# Mechanical.net
KiCad netlist of a schematic drawn in Altium Designer
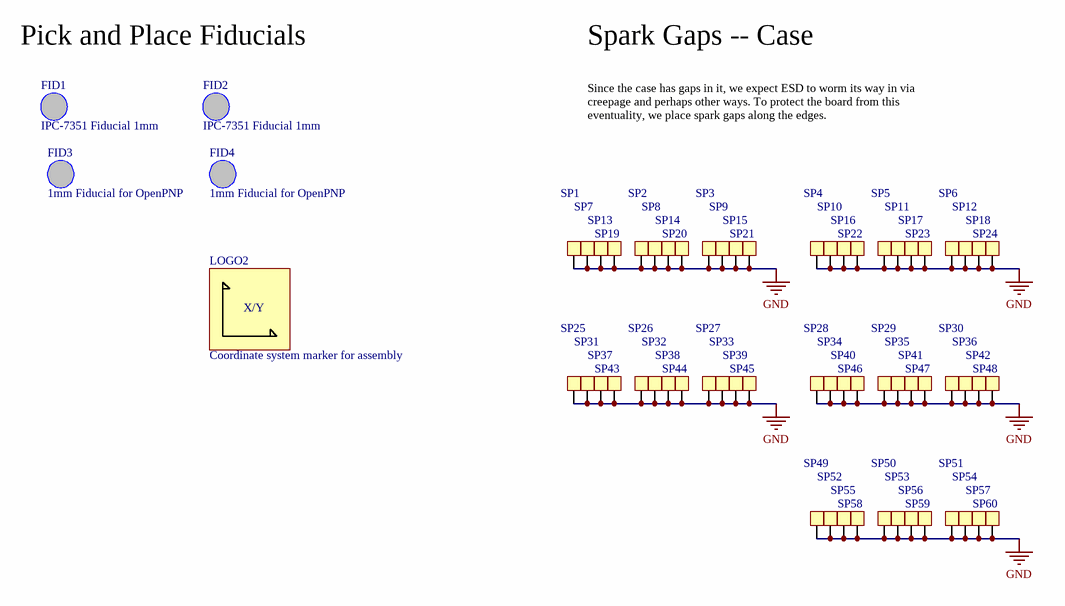
[diagram p0: Mechanical.SchDoc]

(export (version "E")
  (design (tool "Eeschema 10.0.6"))
  (components
    (comp (ref "FID1")
      (value "IPC-7351 Fiducial 1mm")
      (footprint "FIDUCIAL_1.5")
      (libsource (lib "Mechanical") (part "FIDUCIAL_1.5"))
    )
    (comp (ref "FID2")
      (value "IPC-7351 Fiducial 1mm")
      (footprint "FIDUCIAL_1.5")
      (libsource (lib "Mechanical") (part "FIDUCIAL_1.5"))
    )
    (comp (ref "FID3")
      (value "1mm Fiducial for OpenPNP")
      (footprint "FIDUCIAL-NEW")
      (libsource (lib "Mechanical") (part "FIDUCIAL_NEW"))
    )
    (comp (ref "FID4")
      (value "1mm Fiducial for OpenPNP")
      (footprint "FIDUCIAL-NEW")
      (libsource (lib "Mechanical") (part "FIDUCIAL_NEW"))
    )
    (comp (ref "LOGO2")
      (value "Coordinate system marker for assembly")
      (footprint "Coordinate System")
      (libsource (lib "Graphics") (part "CoordinateSystem"))
    )
    (comp (ref "SP1")
      (value "Spark Gap")
      (footprint "SparkGap")
      (description "Open square pad for spark gapping")
      (libsource (lib "PCBFeatures") (part "Spark Gap"))
    )
    (comp (ref "SP2")
      (value "Spark Gap")
      (footprint "SparkGap")
      (description "Open square pad for spark gapping")
      (libsource (lib "PCBFeatures") (part "Spark Gap"))
    )
    (comp (ref "SP3")
      (value "Spark Gap")
      (footprint "SparkGap")
      (description "Open square pad for spark gapping")
      (libsource (lib "PCBFeatures") (part "Spark Gap"))
    )
    (comp (ref "SP4")
      (value "Spark Gap")
      (footprint "SparkGap")
      (description "Open square pad for spark gapping")
      (libsource (lib "PCBFeatures") (part "Spark Gap"))
    )
    (comp (ref "SP5")
      (value "Spark Gap")
      (footprint "SparkGap")
      (description "Open square pad for spark gapping")
      (libsource (lib "PCBFeatures") (part "Spark Gap"))
    )
    (comp (ref "SP6")
      (value "Spark Gap")
      (footprint "SparkGap")
      (description "Open square pad for spark gapping")
      (libsource (lib "PCBFeatures") (part "Spark Gap"))
    )
    (comp (ref "SP7")
      (value "Spark Gap")
      (footprint "SparkGap")
      (description "Open square pad for spark gapping")
      (libsource (lib "PCBFeatures") (part "Spark Gap"))
    )
    (comp (ref "SP8")
      (value "Spark Gap")
      (footprint "SparkGap")
      (description "Open square pad for spark gapping")
      (libsource (lib "PCBFeatures") (part "Spark Gap"))
    )
    (comp (ref "SP9")
      (value "Spark Gap")
      (footprint "SparkGap")
      (description "Open square pad for spark gapping")
      (libsource (lib "PCBFeatures") (part "Spark Gap"))
    )
    (comp (ref "SP10")
      (value "Spark Gap")
      (footprint "SparkGap")
      (description "Open square pad for spark gapping")
      (libsource (lib "PCBFeatures") (part "Spark Gap"))
    )
    (comp (ref "SP11")
      (value "Spark Gap")
      (footprint "SparkGap")
      (description "Open square pad for spark gapping")
      (libsource (lib "PCBFeatures") (part "Spark Gap"))
    )
    (comp (ref "SP12")
      (value "Spark Gap")
      (footprint "SparkGap")
      (description "Open square pad for spark gapping")
      (libsource (lib "PCBFeatures") (part "Spark Gap"))
    )
    (comp (ref "SP13")
      (value "Spark Gap")
      (footprint "SparkGap")
      (description "Open square pad for spark gapping")
      (libsource (lib "PCBFeatures") (part "Spark Gap"))
    )
    (comp (ref "SP14")
      (value "Spark Gap")
      (footprint "SparkGap")
      (description "Open square pad for spark gapping")
      (libsource (lib "PCBFeatures") (part "Spark Gap"))
    )
    (comp (ref "SP15")
      (value "Spark Gap")
      (footprint "SparkGap")
      (description "Open square pad for spark gapping")
      (libsource (lib "PCBFeatures") (part "Spark Gap"))
    )
    (comp (ref "SP16")
      (value "Spark Gap")
      (footprint "SparkGap")
      (description "Open square pad for spark gapping")
      (libsource (lib "PCBFeatures") (part "Spark Gap"))
    )
    (comp (ref "SP17")
      (value "Spark Gap")
      (footprint "SparkGap")
      (description "Open square pad for spark gapping")
      (libsource (lib "PCBFeatures") (part "Spark Gap"))
    )
    (comp (ref "SP18")
      (value "Spark Gap")
      (footprint "SparkGap")
      (description "Open square pad for spark gapping")
      (libsource (lib "PCBFeatures") (part "Spark Gap"))
    )
    (comp (ref "SP19")
      (value "Spark Gap")
      (footprint "SparkGap")
      (description "Open square pad for spark gapping")
      (libsource (lib "PCBFeatures") (part "Spark Gap"))
    )
    (comp (ref "SP20")
      (value "Spark Gap")
      (footprint "SparkGap")
      (description "Open square pad for spark gapping")
      (libsource (lib "PCBFeatures") (part "Spark Gap"))
    )
    (comp (ref "SP21")
      (value "Spark Gap")
      (footprint "SparkGap")
      (description "Open square pad for spark gapping")
      (libsource (lib "PCBFeatures") (part "Spark Gap"))
    )
    (comp (ref "SP22")
      (value "Spark Gap")
      (footprint "SparkGap")
      (description "Open square pad for spark gapping")
      (libsource (lib "PCBFeatures") (part "Spark Gap"))
    )
    (comp (ref "SP23")
      (value "Spark Gap")
      (footprint "SparkGap")
      (description "Open square pad for spark gapping")
      (libsource (lib "PCBFeatures") (part "Spark Gap"))
    )
    (comp (ref "SP24")
      (value "Spark Gap")
      (footprint "SparkGap")
      (description "Open square pad for spark gapping")
      (libsource (lib "PCBFeatures") (part "Spark Gap"))
    )
    (comp (ref "SP25")
      (value "Spark Gap")
      (footprint "SparkGap")
      (description "Open square pad for spark gapping")
      (libsource (lib "PCBFeatures") (part "Spark Gap"))
    )
    (comp (ref "SP26")
      (value "Spark Gap")
      (footprint "SparkGap")
      (description "Open square pad for spark gapping")
      (libsource (lib "PCBFeatures") (part "Spark Gap"))
    )
    (comp (ref "SP27")
      (value "Spark Gap")
      (footprint "SparkGap")
      (description "Open square pad for spark gapping")
      (libsource (lib "PCBFeatures") (part "Spark Gap"))
    )
    (comp (ref "SP28")
      (value "Spark Gap")
      (footprint "SparkGap")
      (description "Open square pad for spark gapping")
      (libsource (lib "PCBFeatures") (part "Spark Gap"))
    )
    (comp (ref "SP29")
      (value "Spark Gap")
      (footprint "SparkGap")
      (description "Open square pad for spark gapping")
      (libsource (lib "PCBFeatures") (part "Spark Gap"))
    )
    (comp (ref "SP30")
      (value "Spark Gap")
      (footprint "SparkGap")
      (description "Open square pad for spark gapping")
      (libsource (lib "PCBFeatures") (part "Spark Gap"))
    )
    (comp (ref "SP31")
      (value "Spark Gap")
      (footprint "SparkGap")
      (description "Open square pad for spark gapping")
      (libsource (lib "PCBFeatures") (part "Spark Gap"))
    )
    (comp (ref "SP32")
      (value "Spark Gap")
      (footprint "SparkGap")
      (description "Open square pad for spark gapping")
      (libsource (lib "PCBFeatures") (part "Spark Gap"))
    )
    (comp (ref "SP33")
      (value "Spark Gap")
      (footprint "SparkGap")
      (description "Open square pad for spark gapping")
      (libsource (lib "PCBFeatures") (part "Spark Gap"))
    )
    (comp (ref "SP34")
      (value "Spark Gap")
      (footprint "SparkGap")
      (description "Open square pad for spark gapping")
      (libsource (lib "PCBFeatures") (part "Spark Gap"))
    )
    (comp (ref "SP35")
      (value "Spark Gap")
      (footprint "SparkGap")
      (description "Open square pad for spark gapping")
      (libsource (lib "PCBFeatures") (part "Spark Gap"))
    )
    (comp (ref "SP36")
      (value "Spark Gap")
      (footprint "SparkGap")
      (description "Open square pad for spark gapping")
      (libsource (lib "PCBFeatures") (part "Spark Gap"))
    )
    (comp (ref "SP37")
      (value "Spark Gap")
      (footprint "SparkGap")
      (description "Open square pad for spark gapping")
      (libsource (lib "PCBFeatures") (part "Spark Gap"))
    )
    (comp (ref "SP38")
      (value "Spark Gap")
      (footprint "SparkGap")
      (description "Open square pad for spark gapping")
      (libsource (lib "PCBFeatures") (part "Spark Gap"))
    )
    (comp (ref "SP39")
      (value "Spark Gap")
      (footprint "SparkGap")
      (description "Open square pad for spark gapping")
      (libsource (lib "PCBFeatures") (part "Spark Gap"))
    )
    (comp (ref "SP40")
      (value "Spark Gap")
      (footprint "SparkGap")
      (description "Open square pad for spark gapping")
      (libsource (lib "PCBFeatures") (part "Spark Gap"))
    )
    (comp (ref "SP41")
      (value "Spark Gap")
      (footprint "SparkGap")
      (description "Open square pad for spark gapping")
      (libsource (lib "PCBFeatures") (part "Spark Gap"))
    )
    (comp (ref "SP42")
      (value "Spark Gap")
      (footprint "SparkGap")
      (description "Open square pad for spark gapping")
      (libsource (lib "PCBFeatures") (part "Spark Gap"))
    )
    (comp (ref "SP43")
      (value "Spark Gap")
      (footprint "SparkGap")
      (description "Open square pad for spark gapping")
      (libsource (lib "PCBFeatures") (part "Spark Gap"))
    )
    (comp (ref "SP44")
      (value "Spark Gap")
      (footprint "SparkGap")
      (description "Open square pad for spark gapping")
      (libsource (lib "PCBFeatures") (part "Spark Gap"))
    )
    (comp (ref "SP45")
      (value "Spark Gap")
      (footprint "SparkGap")
      (description "Open square pad for spark gapping")
      (libsource (lib "PCBFeatures") (part "Spark Gap"))
    )
    (comp (ref "SP46")
      (value "Spark Gap")
      (footprint "SparkGap")
      (description "Open square pad for spark gapping")
      (libsource (lib "PCBFeatures") (part "Spark Gap"))
    )
    (comp (ref "SP47")
      (value "Spark Gap")
      (footprint "SparkGap")
      (description "Open square pad for spark gapping")
      (libsource (lib "PCBFeatures") (part "Spark Gap"))
    )
    (comp (ref "SP48")
      (value "Spark Gap")
      (footprint "SparkGap")
      (description "Open square pad for spark gapping")
      (libsource (lib "PCBFeatures") (part "Spark Gap"))
    )
    (comp (ref "SP49")
      (value "Spark Gap")
      (footprint "SparkGap")
      (description "Open square pad for spark gapping")
      (libsource (lib "PCBFeatures") (part "Spark Gap"))
    )
    (comp (ref "SP50")
      (value "Spark Gap")
      (footprint "SparkGap")
      (description "Open square pad for spark gapping")
      (libsource (lib "PCBFeatures") (part "Spark Gap"))
    )
    (comp (ref "SP51")
      (value "Spark Gap")
      (footprint "SparkGap")
      (description "Open square pad for spark gapping")
      (libsource (lib "PCBFeatures") (part "Spark Gap"))
    )
    (comp (ref "SP52")
      (value "Spark Gap")
      (footprint "SparkGap")
      (description "Open square pad for spark gapping")
      (libsource (lib "PCBFeatures") (part "Spark Gap"))
    )
    (comp (ref "SP53")
      (value "Spark Gap")
      (footprint "SparkGap")
      (description "Open square pad for spark gapping")
      (libsource (lib "PCBFeatures") (part "Spark Gap"))
    )
    (comp (ref "SP54")
      (value "Spark Gap")
      (footprint "SparkGap")
      (description "Open square pad for spark gapping")
      (libsource (lib "PCBFeatures") (part "Spark Gap"))
    )
    (comp (ref "SP55")
      (value "Spark Gap")
      (footprint "SparkGap")
      (description "Open square pad for spark gapping")
      (libsource (lib "PCBFeatures") (part "Spark Gap"))
    )
    (comp (ref "SP56")
      (value "Spark Gap")
      (footprint "SparkGap")
      (description "Open square pad for spark gapping")
      (libsource (lib "PCBFeatures") (part "Spark Gap"))
    )
    (comp (ref "SP57")
      (value "Spark Gap")
      (footprint "SparkGap")
      (description "Open square pad for spark gapping")
      (libsource (lib "PCBFeatures") (part "Spark Gap"))
    )
    (comp (ref "SP58")
      (value "Spark Gap")
      (footprint "SparkGap")
      (description "Open square pad for spark gapping")
      (libsource (lib "PCBFeatures") (part "Spark Gap"))
    )
    (comp (ref "SP59")
      (value "Spark Gap")
      (footprint "SparkGap")
      (description "Open square pad for spark gapping")
      (libsource (lib "PCBFeatures") (part "Spark Gap"))
    )
    (comp (ref "SP60")
      (value "Spark Gap")
      (footprint "SparkGap")
      (description "Open square pad for spark gapping")
      (libsource (lib "PCBFeatures") (part "Spark Gap"))
    )
  )
  (nets
    (net (code "1") (name "GND") (class "Default")
      (node (ref "SP1") (pin "1") (pinfunction "1_1") (pintype "passive"))
      (node (ref "SP10") (pin "1") (pinfunction "1_1") (pintype "passive"))
      (node (ref "SP11") (pin "1") (pinfunction "1_1") (pintype "passive"))
      (node (ref "SP12") (pin "1") (pinfunction "1_1") (pintype "passive"))
      (node (ref "SP13") (pin "1") (pinfunction "1_1") (pintype "passive"))
      (node (ref "SP14") (pin "1") (pinfunction "1_1") (pintype "passive"))
      (node (ref "SP15") (pin "1") (pinfunction "1_1") (pintype "passive"))
      (node (ref "SP16") (pin "1") (pinfunction "1_1") (pintype "passive"))
      (node (ref "SP17") (pin "1") (pinfunction "1_1") (pintype "passive"))
      (node (ref "SP18") (pin "1") (pinfunction "1_1") (pintype "passive"))
      (node (ref "SP19") (pin "1") (pinfunction "1_1") (pintype "passive"))
      (node (ref "SP2") (pin "1") (pinfunction "1_1") (pintype "passive"))
      (node (ref "SP20") (pin "1") (pinfunction "1_1") (pintype "passive"))
      (node (ref "SP21") (pin "1") (pinfunction "1_1") (pintype "passive"))
      (node (ref "SP22") (pin "1") (pinfunction "1_1") (pintype "passive"))
      (node (ref "SP23") (pin "1") (pinfunction "1_1") (pintype "passive"))
      (node (ref "SP24") (pin "1") (pinfunction "1_1") (pintype "passive"))
      (node (ref "SP25") (pin "1") (pinfunction "1_1") (pintype "passive"))
      (node (ref "SP26") (pin "1") (pinfunction "1_1") (pintype "passive"))
      (node (ref "SP27") (pin "1") (pinfunction "1_1") (pintype "passive"))
      (node (ref "SP28") (pin "1") (pinfunction "1_1") (pintype "passive"))
      (node (ref "SP29") (pin "1") (pinfunction "1_1") (pintype "passive"))
      (node (ref "SP3") (pin "1") (pinfunction "1_1") (pintype "passive"))
      (node (ref "SP30") (pin "1") (pinfunction "1_1") (pintype "passive"))
      (node (ref "SP31") (pin "1") (pinfunction "1_1") (pintype "passive"))
      (node (ref "SP32") (pin "1") (pinfunction "1_1") (pintype "passive"))
      (node (ref "SP33") (pin "1") (pinfunction "1_1") (pintype "passive"))
      (node (ref "SP34") (pin "1") (pinfunction "1_1") (pintype "passive"))
      (node (ref "SP35") (pin "1") (pinfunction "1_1") (pintype "passive"))
      (node (ref "SP36") (pin "1") (pinfunction "1_1") (pintype "passive"))
      (node (ref "SP37") (pin "1") (pinfunction "1_1") (pintype "passive"))
      (node (ref "SP38") (pin "1") (pinfunction "1_1") (pintype "passive"))
      (node (ref "SP39") (pin "1") (pinfunction "1_1") (pintype "passive"))
      (node (ref "SP4") (pin "1") (pinfunction "1_1") (pintype "passive"))
      (node (ref "SP40") (pin "1") (pinfunction "1_1") (pintype "passive"))
      (node (ref "SP41") (pin "1") (pinfunction "1_1") (pintype "passive"))
      (node (ref "SP42") (pin "1") (pinfunction "1_1") (pintype "passive"))
      (node (ref "SP43") (pin "1") (pinfunction "1_1") (pintype "passive"))
      (node (ref "SP44") (pin "1") (pinfunction "1_1") (pintype "passive"))
      (node (ref "SP45") (pin "1") (pinfunction "1_1") (pintype "passive"))
      (node (ref "SP46") (pin "1") (pinfunction "1_1") (pintype "passive"))
      (node (ref "SP47") (pin "1") (pinfunction "1_1") (pintype "passive"))
      (node (ref "SP48") (pin "1") (pinfunction "1_1") (pintype "passive"))
      (node (ref "SP49") (pin "1") (pinfunction "1_1") (pintype "passive"))
      (node (ref "SP5") (pin "1") (pinfunction "1_1") (pintype "passive"))
      (node (ref "SP50") (pin "1") (pinfunction "1_1") (pintype "passive"))
      (node (ref "SP51") (pin "1") (pinfunction "1_1") (pintype "passive"))
      (node (ref "SP52") (pin "1") (pinfunction "1_1") (pintype "passive"))
      (node (ref "SP53") (pin "1") (pinfunction "1_1") (pintype "passive"))
      (node (ref "SP54") (pin "1") (pinfunction "1_1") (pintype "passive"))
      (node (ref "SP55") (pin "1") (pinfunction "1_1") (pintype "passive"))
      (node (ref "SP56") (pin "1") (pinfunction "1_1") (pintype "passive"))
      (node (ref "SP57") (pin "1") (pinfunction "1_1") (pintype "passive"))
      (node (ref "SP58") (pin "1") (pinfunction "1_1") (pintype "passive"))
      (node (ref "SP59") (pin "1") (pinfunction "1_1") (pintype "passive"))
      (node (ref "SP6") (pin "1") (pinfunction "1_1") (pintype "passive"))
      (node (ref "SP60") (pin "1") (pinfunction "1_1") (pintype "passive"))
      (node (ref "SP7") (pin "1") (pinfunction "1_1") (pintype "passive"))
      (node (ref "SP8") (pin "1") (pinfunction "1_1") (pintype "passive"))
      (node (ref "SP9") (pin "1") (pinfunction "1_1") (pintype "passive"))
    )
    (net (code "2") (name "unconnected-(FID1-Pad1)") (class "Default")
      (node (ref "FID1") (pin "1") (pinfunction "1_1") (pintype "passive"))
    )
    (net (code "3") (name "unconnected-(FID2-Pad1)") (class "Default")
      (node (ref "FID2") (pin "1") (pinfunction "1_1") (pintype "passive"))
    )
    (net (code "4") (name "unconnected-(FID3-Pad1)") (class "Default")
      (node (ref "FID3") (pin "1") (pinfunction "1_1") (pintype "passive"))
    )
    (net (code "5") (name "unconnected-(FID4-Pad1)") (class "Default")
      (node (ref "FID4") (pin "1") (pinfunction "1_1") (pintype "passive"))
    )
  )
)
